# board.net
KiCad netlist of a schematic drawn in EAGLE
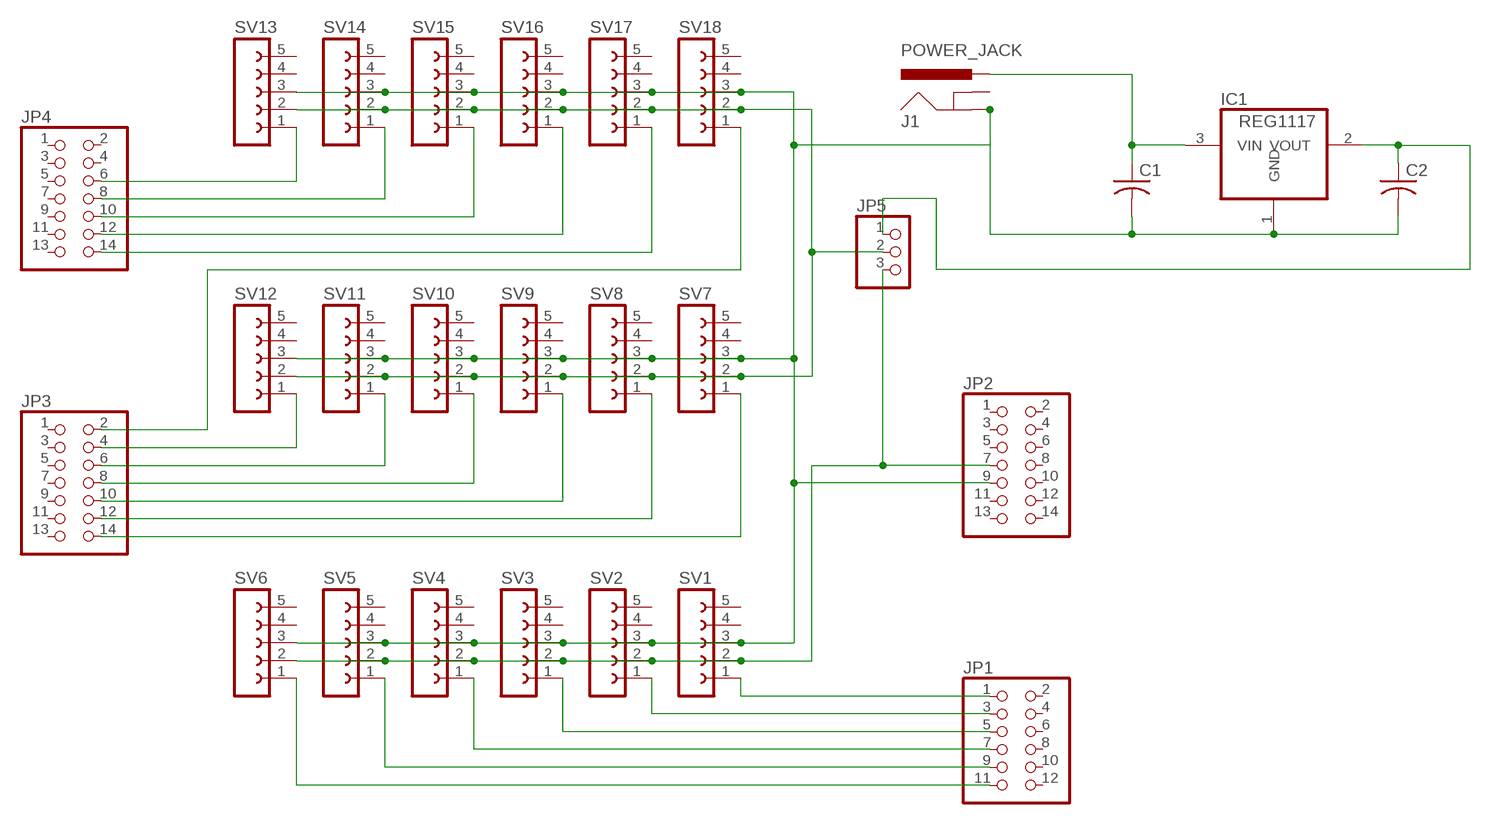
[diagram p0: schematic, sheet 1]

(export (version "E")
  (design (tool "Eeschema 10.0.6"))
  (components
    (comp (ref "C1")
      (value "C-US025-024X044")
      (footprint "eagle-import:C025-024X044")
      (libsource (lib "eagle-import") (part "C-US025-024X044"))
    )
    (comp (ref "C2")
      (value "C-US025-024X044")
      (footprint "eagle-import:C025-024X044")
      (libsource (lib "eagle-import") (part "C-US025-024X044"))
    )
    (comp (ref "IC1")
      (value "REG1117")
      (footprint "eagle-import:SOT223")
      (libsource (lib "eagle-import") (part "REG1117"))
    )
    (comp (ref "J1")
      (value "POWER_JACK")
      (footprint "eagle-import:POWER_JACK_PTH")
      (libsource (lib "eagle-import") (part "POWER_JACK"))
    )
    (comp (ref "JP1")
      (value "PINHD-2X6")
      (footprint "eagle-import:2X06")
      (libsource (lib "eagle-import") (part "PINHD-2X6"))
    )
    (comp (ref "JP2")
      (value "PINHD-2X7")
      (footprint "eagle-import:2X07")
      (libsource (lib "eagle-import") (part "PINHD-2X7"))
    )
    (comp (ref "JP3")
      (value "PINHD-2X7")
      (footprint "eagle-import:2X07")
      (libsource (lib "eagle-import") (part "PINHD-2X7"))
    )
    (comp (ref "JP4")
      (value "PINHD-2X7")
      (footprint "eagle-import:2X07")
      (libsource (lib "eagle-import") (part "PINHD-2X7"))
    )
    (comp (ref "JP5")
      (value "PINHD-1X3")
      (footprint "eagle-import:1X03")
      (libsource (lib "eagle-import") (part "PINHD-1X3"))
    )
    (comp (ref "SV1")
      (value "FE05-1")
      (footprint "eagle-import:FE05-1")
      (libsource (lib "eagle-import") (part "FE05-1"))
    )
    (comp (ref "SV2")
      (value "FE05-1")
      (footprint "eagle-import:FE05-1")
      (libsource (lib "eagle-import") (part "FE05-1"))
    )
    (comp (ref "SV3")
      (value "FE05-1")
      (footprint "eagle-import:FE05-1")
      (libsource (lib "eagle-import") (part "FE05-1"))
    )
    (comp (ref "SV4")
      (value "FE05-1")
      (footprint "eagle-import:FE05-1")
      (libsource (lib "eagle-import") (part "FE05-1"))
    )
    (comp (ref "SV5")
      (value "FE05-1")
      (footprint "eagle-import:FE05-1")
      (libsource (lib "eagle-import") (part "FE05-1"))
    )
    (comp (ref "SV6")
      (value "FE05-1")
      (footprint "eagle-import:FE05-1")
      (libsource (lib "eagle-import") (part "FE05-1"))
    )
    (comp (ref "SV7")
      (value "FE05-1")
      (footprint "eagle-import:FE05-1")
      (libsource (lib "eagle-import") (part "FE05-1"))
    )
    (comp (ref "SV8")
      (value "FE05-1")
      (footprint "eagle-import:FE05-1")
      (libsource (lib "eagle-import") (part "FE05-1"))
    )
    (comp (ref "SV9")
      (value "FE05-1")
      (footprint "eagle-import:FE05-1")
      (libsource (lib "eagle-import") (part "FE05-1"))
    )
    (comp (ref "SV10")
      (value "FE05-1")
      (footprint "eagle-import:FE05-1")
      (libsource (lib "eagle-import") (part "FE05-1"))
    )
    (comp (ref "SV11")
      (value "FE05-1")
      (footprint "eagle-import:FE05-1")
      (libsource (lib "eagle-import") (part "FE05-1"))
    )
    (comp (ref "SV12")
      (value "FE05-1")
      (footprint "eagle-import:FE05-1")
      (libsource (lib "eagle-import") (part "FE05-1"))
    )
    (comp (ref "SV13")
      (value "FE05-1")
      (footprint "eagle-import:FE05-1")
      (libsource (lib "eagle-import") (part "FE05-1"))
    )
    (comp (ref "SV14")
      (value "FE05-1")
      (footprint "eagle-import:FE05-1")
      (libsource (lib "eagle-import") (part "FE05-1"))
    )
    (comp (ref "SV15")
      (value "FE05-1")
      (footprint "eagle-import:FE05-1")
      (libsource (lib "eagle-import") (part "FE05-1"))
    )
    (comp (ref "SV16")
      (value "FE05-1")
      (footprint "eagle-import:FE05-1")
      (libsource (lib "eagle-import") (part "FE05-1"))
    )
    (comp (ref "SV17")
      (value "FE05-1")
      (footprint "eagle-import:FE05-1")
      (libsource (lib "eagle-import") (part "FE05-1"))
    )
    (comp (ref "SV18")
      (value "FE05-1")
      (footprint "eagle-import:FE05-1")
      (libsource (lib "eagle-import") (part "FE05-1"))
    )
  )
  (nets
    (net (code "1") (name "Net-(IC1-GND)") (class "Default")
      (node (ref "C1") (pin "2") (pinfunction "2_2") (pintype "passive"))
      (node (ref "C2") (pin "2") (pinfunction "2_2") (pintype "passive"))
      (node (ref "IC1") (pin "1") (pinfunction "GND_1") (pintype "power_in"))
      (node (ref "J1") (pin "GND") (pinfunction "GND_GND") (pintype "bidirectional"))
      (node (ref "JP2") (pin "9") (pinfunction "9_9") (pintype "passive"))
      (node (ref "SV1") (pin "3") (pinfunction "3_3") (pintype "passive"))
      (node (ref "SV10") (pin "3") (pinfunction "3_3") (pintype "passive"))
      (node (ref "SV11") (pin "3") (pinfunction "3_3") (pintype "passive"))
      (node (ref "SV12") (pin "3") (pinfunction "3_3") (pintype "passive"))
      (node (ref "SV13") (pin "3") (pinfunction "3_3") (pintype "passive"))
      (node (ref "SV14") (pin "3") (pinfunction "3_3") (pintype "passive"))
      (node (ref "SV15") (pin "3") (pinfunction "3_3") (pintype "passive"))
      (node (ref "SV16") (pin "3") (pinfunction "3_3") (pintype "passive"))
      (node (ref "SV17") (pin "3") (pinfunction "3_3") (pintype "passive"))
      (node (ref "SV18") (pin "3") (pinfunction "3_3") (pintype "passive"))
      (node (ref "SV2") (pin "3") (pinfunction "3_3") (pintype "passive"))
      (node (ref "SV3") (pin "3") (pinfunction "3_3") (pintype "passive"))
      (node (ref "SV4") (pin "3") (pinfunction "3_3") (pintype "passive"))
      (node (ref "SV5") (pin "3") (pinfunction "3_3") (pintype "passive"))
      (node (ref "SV6") (pin "3") (pinfunction "3_3") (pintype "passive"))
      (node (ref "SV7") (pin "3") (pinfunction "3_3") (pintype "passive"))
      (node (ref "SV8") (pin "3") (pinfunction "3_3") (pintype "passive"))
      (node (ref "SV9") (pin "3") (pinfunction "3_3") (pintype "passive"))
    )
    (net (code "2") (name "Net-(IC1-VIN)") (class "Default")
      (node (ref "C1") (pin "1") (pinfunction "1_1") (pintype "passive"))
      (node (ref "IC1") (pin "3") (pinfunction "VIN_3") (pintype "input"))
      (node (ref "J1") (pin "PWR") (pinfunction "PWR_PWR") (pintype "bidirectional"))
    )
    (net (code "3") (name "Net-(IC1-VOUT)") (class "Default")
      (node (ref "C2") (pin "1") (pinfunction "1_1") (pintype "passive"))
      (node (ref "IC1") (pin "2") (pinfunction "VOUT_2") (pintype "output"))
      (node (ref "JP5") (pin "1") (pinfunction "1_1") (pintype "passive"))
    )
    (net (code "4") (name "Net-(JP1-Pad1)") (class "Default")
      (node (ref "JP1") (pin "1") (pinfunction "1_1") (pintype "passive"))
      (node (ref "SV1") (pin "1") (pinfunction "1_1") (pintype "passive"))
    )
    (net (code "5") (name "Net-(JP1-Pad3)") (class "Default")
      (node (ref "JP1") (pin "3") (pinfunction "3_3") (pintype "passive"))
      (node (ref "SV2") (pin "1") (pinfunction "1_1") (pintype "passive"))
    )
    (net (code "6") (name "Net-(JP1-Pad5)") (class "Default")
      (node (ref "JP1") (pin "5") (pinfunction "5_5") (pintype "passive"))
      (node (ref "SV3") (pin "1") (pinfunction "1_1") (pintype "passive"))
    )
    (net (code "7") (name "Net-(JP1-Pad7)") (class "Default")
      (node (ref "JP1") (pin "7") (pinfunction "7_7") (pintype "passive"))
      (node (ref "SV4") (pin "1") (pinfunction "1_1") (pintype "passive"))
    )
    (net (code "8") (name "Net-(JP1-Pad9)") (class "Default")
      (node (ref "JP1") (pin "9") (pinfunction "9_9") (pintype "passive"))
      (node (ref "SV5") (pin "1") (pinfunction "1_1") (pintype "passive"))
    )
    (net (code "9") (name "Net-(JP1-Pad11)") (class "Default")
      (node (ref "JP1") (pin "11") (pinfunction "11_11") (pintype "passive"))
      (node (ref "SV6") (pin "1") (pinfunction "1_1") (pintype "passive"))
    )
    (net (code "10") (name "Net-(JP2-Pad7)") (class "Default")
      (node (ref "JP2") (pin "7") (pinfunction "7_7") (pintype "passive"))
      (node (ref "JP5") (pin "3") (pinfunction "3_3") (pintype "passive"))
      (node (ref "SV1") (pin "2") (pinfunction "2_2") (pintype "passive"))
      (node (ref "SV2") (pin "2") (pinfunction "2_2") (pintype "passive"))
      (node (ref "SV3") (pin "2") (pinfunction "2_2") (pintype "passive"))
      (node (ref "SV4") (pin "2") (pinfunction "2_2") (pintype "passive"))
      (node (ref "SV5") (pin "2") (pinfunction "2_2") (pintype "passive"))
      (node (ref "SV6") (pin "2") (pinfunction "2_2") (pintype "passive"))
    )
    (net (code "11") (name "Net-(JP3-Pad2)") (class "Default")
      (node (ref "JP3") (pin "2") (pinfunction "2_2") (pintype "passive"))
      (node (ref "SV18") (pin "1") (pinfunction "1_1") (pintype "passive"))
    )
    (net (code "12") (name "Net-(JP3-Pad4)") (class "Default")
      (node (ref "JP3") (pin "4") (pinfunction "4_4") (pintype "passive"))
      (node (ref "SV12") (pin "1") (pinfunction "1_1") (pintype "passive"))
    )
    (net (code "13") (name "Net-(JP3-Pad6)") (class "Default")
      (node (ref "JP3") (pin "6") (pinfunction "6_6") (pintype "passive"))
      (node (ref "SV11") (pin "1") (pinfunction "1_1") (pintype "passive"))
    )
    (net (code "14") (name "Net-(JP3-Pad8)") (class "Default")
      (node (ref "JP3") (pin "8") (pinfunction "8_8") (pintype "passive"))
      (node (ref "SV10") (pin "1") (pinfunction "1_1") (pintype "passive"))
    )
    (net (code "15") (name "Net-(JP3-Pad10)") (class "Default")
      (node (ref "JP3") (pin "10") (pinfunction "10_10") (pintype "passive"))
      (node (ref "SV9") (pin "1") (pinfunction "1_1") (pintype "passive"))
    )
    (net (code "16") (name "Net-(JP3-Pad12)") (class "Default")
      (node (ref "JP3") (pin "12") (pinfunction "12_12") (pintype "passive"))
      (node (ref "SV8") (pin "1") (pinfunction "1_1") (pintype "passive"))
    )
    (net (code "17") (name "Net-(JP3-Pad14)") (class "Default")
      (node (ref "JP3") (pin "14") (pinfunction "14_14") (pintype "passive"))
      (node (ref "SV7") (pin "1") (pinfunction "1_1") (pintype "passive"))
    )
    (net (code "18") (name "Net-(JP4-Pad6)") (class "Default")
      (node (ref "JP4") (pin "6") (pinfunction "6_6") (pintype "passive"))
      (node (ref "SV13") (pin "1") (pinfunction "1_1") (pintype "passive"))
    )
    (net (code "19") (name "Net-(JP4-Pad8)") (class "Default")
      (node (ref "JP4") (pin "8") (pinfunction "8_8") (pintype "passive"))
      (node (ref "SV14") (pin "1") (pinfunction "1_1") (pintype "passive"))
    )
    (net (code "20") (name "Net-(JP4-Pad10)") (class "Default")
      (node (ref "JP4") (pin "10") (pinfunction "10_10") (pintype "passive"))
      (node (ref "SV15") (pin "1") (pinfunction "1_1") (pintype "passive"))
    )
    (net (code "21") (name "Net-(JP4-Pad12)") (class "Default")
      (node (ref "JP4") (pin "12") (pinfunction "12_12") (pintype "passive"))
      (node (ref "SV16") (pin "1") (pinfunction "1_1") (pintype "passive"))
    )
    (net (code "22") (name "Net-(JP4-Pad14)") (class "Default")
      (node (ref "JP4") (pin "14") (pinfunction "14_14") (pintype "passive"))
      (node (ref "SV17") (pin "1") (pinfunction "1_1") (pintype "passive"))
    )
    (net (code "23") (name "Net-(JP5-Pad2)") (class "Default")
      (node (ref "JP5") (pin "2") (pinfunction "2_2") (pintype "passive"))
      (node (ref "SV10") (pin "2") (pinfunction "2_2") (pintype "passive"))
      (node (ref "SV11") (pin "2") (pinfunction "2_2") (pintype "passive"))
      (node (ref "SV12") (pin "2") (pinfunction "2_2") (pintype "passive"))
      (node (ref "SV13") (pin "2") (pinfunction "2_2") (pintype "passive"))
      (node (ref "SV14") (pin "2") (pinfunction "2_2") (pintype "passive"))
      (node (ref "SV15") (pin "2") (pinfunction "2_2") (pintype "passive"))
      (node (ref "SV16") (pin "2") (pinfunction "2_2") (pintype "passive"))
      (node (ref "SV17") (pin "2") (pinfunction "2_2") (pintype "passive"))
      (node (ref "SV18") (pin "2") (pinfunction "2_2") (pintype "passive"))
      (node (ref "SV7") (pin "2") (pinfunction "2_2") (pintype "passive"))
      (node (ref "SV8") (pin "2") (pinfunction "2_2") (pintype "passive"))
      (node (ref "SV9") (pin "2") (pinfunction "2_2") (pintype "passive"))
    )
    (net (code "24") (name "unconnected-(J1-PadGNDBREAK)") (class "Default")
      (node (ref "J1") (pin "GNDBREAK") (pinfunction "GNDBREAK_GNDBREAK") (pintype "bidirectional"))
    )
    (net (code "25") (name "unconnected-(JP1-Pad2)") (class "Default")
      (node (ref "JP1") (pin "2") (pinfunction "2_2") (pintype "passive"))
    )
    (net (code "26") (name "unconnected-(JP1-Pad4)") (class "Default")
      (node (ref "JP1") (pin "4") (pinfunction "4_4") (pintype "passive"))
    )
    (net (code "27") (name "unconnected-(JP1-Pad6)") (class "Default")
      (node (ref "JP1") (pin "6") (pinfunction "6_6") (pintype "passive"))
    )
    (net (code "28") (name "unconnected-(JP1-Pad8)") (class "Default")
      (node (ref "JP1") (pin "8") (pinfunction "8_8") (pintype "passive"))
    )
    (net (code "29") (name "unconnected-(JP1-Pad10)") (class "Default")
      (node (ref "JP1") (pin "10") (pinfunction "10_10") (pintype "passive"))
    )
    (net (code "30") (name "unconnected-(JP1-Pad12)") (class "Default")
      (node (ref "JP1") (pin "12") (pinfunction "12_12") (pintype "passive"))
    )
    (net (code "31") (name "unconnected-(JP2-Pad1)") (class "Default")
      (node (ref "JP2") (pin "1") (pinfunction "1_1") (pintype "passive"))
    )
    (net (code "32") (name "unconnected-(JP2-Pad2)") (class "Default")
      (node (ref "JP2") (pin "2") (pinfunction "2_2") (pintype "passive"))
    )
    (net (code "33") (name "unconnected-(JP2-Pad3)") (class "Default")
      (node (ref "JP2") (pin "3") (pinfunction "3_3") (pintype "passive"))
    )
    (net (code "34") (name "unconnected-(JP2-Pad4)") (class "Default")
      (node (ref "JP2") (pin "4") (pinfunction "4_4") (pintype "passive"))
    )
    (net (code "35") (name "unconnected-(JP2-Pad5)") (class "Default")
      (node (ref "JP2") (pin "5") (pinfunction "5_5") (pintype "passive"))
    )
    (net (code "36") (name "unconnected-(JP2-Pad6)") (class "Default")
      (node (ref "JP2") (pin "6") (pinfunction "6_6") (pintype "passive"))
    )
    (net (code "37") (name "unconnected-(JP2-Pad8)") (class "Default")
      (node (ref "JP2") (pin "8") (pinfunction "8_8") (pintype "passive"))
    )
    (net (code "38") (name "unconnected-(JP2-Pad10)") (class "Default")
      (node (ref "JP2") (pin "10") (pinfunction "10_10") (pintype "passive"))
    )
    (net (code "39") (name "unconnected-(JP2-Pad11)") (class "Default")
      (node (ref "JP2") (pin "11") (pinfunction "11_11") (pintype "passive"))
    )
    (net (code "40") (name "unconnected-(JP2-Pad12)") (class "Default")
      (node (ref "JP2") (pin "12") (pinfunction "12_12") (pintype "passive"))
    )
    (net (code "41") (name "unconnected-(JP2-Pad13)") (class "Default")
      (node (ref "JP2") (pin "13") (pinfunction "13_13") (pintype "passive"))
    )
    (net (code "42") (name "unconnected-(JP2-Pad14)") (class "Default")
      (node (ref "JP2") (pin "14") (pinfunction "14_14") (pintype "passive"))
    )
    (net (code "43") (name "unconnected-(JP3-Pad1)") (class "Default")
      (node (ref "JP3") (pin "1") (pinfunction "1_1") (pintype "passive"))
    )
    (net (code "44") (name "unconnected-(JP3-Pad3)") (class "Default")
      (node (ref "JP3") (pin "3") (pinfunction "3_3") (pintype "passive"))
    )
    (net (code "45") (name "unconnected-(JP3-Pad5)") (class "Default")
      (node (ref "JP3") (pin "5") (pinfunction "5_5") (pintype "passive"))
    )
    (net (code "46") (name "unconnected-(JP3-Pad7)") (class "Default")
      (node (ref "JP3") (pin "7") (pinfunction "7_7") (pintype "passive"))
    )
    (net (code "47") (name "unconnected-(JP3-Pad9)") (class "Default")
      (node (ref "JP3") (pin "9") (pinfunction "9_9") (pintype "passive"))
    )
    (net (code "48") (name "unconnected-(JP3-Pad11)") (class "Default")
      (node (ref "JP3") (pin "11") (pinfunction "11_11") (pintype "passive"))
    )
    (net (code "49") (name "unconnected-(JP3-Pad13)") (class "Default")
      (node (ref "JP3") (pin "13") (pinfunction "13_13") (pintype "passive"))
    )
    (net (code "50") (name "unconnected-(JP4-Pad1)") (class "Default")
      (node (ref "JP4") (pin "1") (pinfunction "1_1") (pintype "passive"))
    )
    (net (code "51") (name "unconnected-(JP4-Pad2)") (class "Default")
      (node (ref "JP4") (pin "2") (pinfunction "2_2") (pintype "passive"))
    )
    (net (code "52") (name "unconnected-(JP4-Pad3)") (class "Default")
      (node (ref "JP4") (pin "3") (pinfunction "3_3") (pintype "passive"))
    )
    (net (code "53") (name "unconnected-(JP4-Pad4)") (class "Default")
      (node (ref "JP4") (pin "4") (pinfunction "4_4") (pintype "passive"))
    )
    (net (code "54") (name "unconnected-(JP4-Pad5)") (class "Default")
      (node (ref "JP4") (pin "5") (pinfunction "5_5") (pintype "passive"))
    )
    (net (code "55") (name "unconnected-(JP4-Pad7)") (class "Default")
      (node (ref "JP4") (pin "7") (pinfunction "7_7") (pintype "passive"))
    )
    (net (code "56") (name "unconnected-(JP4-Pad9)") (class "Default")
      (node (ref "JP4") (pin "9") (pinfunction "9_9") (pintype "passive"))
    )
    (net (code "57") (name "unconnected-(JP4-Pad11)") (class "Default")
      (node (ref "JP4") (pin "11") (pinfunction "11_11") (pintype "passive"))
    )
    (net (code "58") (name "unconnected-(JP4-Pad13)") (class "Default")
      (node (ref "JP4") (pin "13") (pinfunction "13_13") (pintype "passive"))
    )
    (net (code "59") (name "unconnected-(SV1-Pad4)") (class "Default")
      (node (ref "SV1") (pin "4") (pinfunction "4_4") (pintype "passive"))
    )
    (net (code "60") (name "unconnected-(SV1-Pad5)") (class "Default")
      (node (ref "SV1") (pin "5") (pinfunction "5_5") (pintype "passive"))
    )
    (net (code "61") (name "unconnected-(SV2-Pad4)") (class "Default")
      (node (ref "SV2") (pin "4") (pinfunction "4_4") (pintype "passive"))
    )
    (net (code "62") (name "unconnected-(SV2-Pad5)") (class "Default")
      (node (ref "SV2") (pin "5") (pinfunction "5_5") (pintype "passive"))
    )
    (net (code "63") (name "unconnected-(SV3-Pad4)") (class "Default")
      (node (ref "SV3") (pin "4") (pinfunction "4_4") (pintype "passive"))
    )
    (net (code "64") (name "unconnected-(SV3-Pad5)") (class "Default")
      (node (ref "SV3") (pin "5") (pinfunction "5_5") (pintype "passive"))
    )
    (net (code "65") (name "unconnected-(SV4-Pad4)") (class "Default")
      (node (ref "SV4") (pin "4") (pinfunction "4_4") (pintype "passive"))
    )
    (net (code "66") (name "unconnected-(SV4-Pad5)") (class "Default")
      (node (ref "SV4") (pin "5") (pinfunction "5_5") (pintype "passive"))
    )
    (net (code "67") (name "unconnected-(SV5-Pad4)") (class "Default")
      (node (ref "SV5") (pin "4") (pinfunction "4_4") (pintype "passive"))
    )
    (net (code "68") (name "unconnected-(SV5-Pad5)") (class "Default")
      (node (ref "SV5") (pin "5") (pinfunction "5_5") (pintype "passive"))
    )
    (net (code "69") (name "unconnected-(SV6-Pad4)") (class "Default")
      (node (ref "SV6") (pin "4") (pinfunction "4_4") (pintype "passive"))
    )
    (net (code "70") (name "unconnected-(SV6-Pad5)") (class "Default")
      (node (ref "SV6") (pin "5") (pinfunction "5_5") (pintype "passive"))
    )
    (net (code "71") (name "unconnected-(SV7-Pad4)") (class "Default")
      (node (ref "SV7") (pin "4") (pinfunction "4_4") (pintype "passive"))
    )
    (net (code "72") (name "unconnected-(SV7-Pad5)") (class "Default")
      (node (ref "SV7") (pin "5") (pinfunction "5_5") (pintype "passive"))
    )
    (net (code "73") (name "unconnected-(SV8-Pad4)") (class "Default")
      (node (ref "SV8") (pin "4") (pinfunction "4_4") (pintype "passive"))
    )
    (net (code "74") (name "unconnected-(SV8-Pad5)") (class "Default")
      (node (ref "SV8") (pin "5") (pinfunction "5_5") (pintype "passive"))
    )
    (net (code "75") (name "unconnected-(SV9-Pad4)") (class "Default")
      (node (ref "SV9") (pin "4") (pinfunction "4_4") (pintype "passive"))
    )
    (net (code "76") (name "unconnected-(SV9-Pad5)") (class "Default")
      (node (ref "SV9") (pin "5") (pinfunction "5_5") (pintype "passive"))
    )
    (net (code "77") (name "unconnected-(SV10-Pad4)") (class "Default")
      (node (ref "SV10") (pin "4") (pinfunction "4_4") (pintype "passive"))
    )
    (net (code "78") (name "unconnected-(SV10-Pad5)") (class "Default")
      (node (ref "SV10") (pin "5") (pinfunction "5_5") (pintype "passive"))
    )
    (net (code "79") (name "unconnected-(SV11-Pad4)") (class "Default")
      (node (ref "SV11") (pin "4") (pinfunction "4_4") (pintype "passive"))
    )
    (net (code "80") (name "unconnected-(SV11-Pad5)") (class "Default")
      (node (ref "SV11") (pin "5") (pinfunction "5_5") (pintype "passive"))
    )
    (net (code "81") (name "unconnected-(SV12-Pad4)") (class "Default")
      (node (ref "SV12") (pin "4") (pinfunction "4_4") (pintype "passive"))
    )
    (net (code "82") (name "unconnected-(SV12-Pad5)") (class "Default")
      (node (ref "SV12") (pin "5") (pinfunction "5_5") (pintype "passive"))
    )
    (net (code "83") (name "unconnected-(SV13-Pad4)") (class "Default")
      (node (ref "SV13") (pin "4") (pinfunction "4_4") (pintype "passive"))
    )
    (net (code "84") (name "unconnected-(SV13-Pad5)") (class "Default")
      (node (ref "SV13") (pin "5") (pinfunction "5_5") (pintype "passive"))
    )
    (net (code "85") (name "unconnected-(SV14-Pad4)") (class "Default")
      (node (ref "SV14") (pin "4") (pinfunction "4_4") (pintype "passive"))
    )
    (net (code "86") (name "unconnected-(SV14-Pad5)") (class "Default")
      (node (ref "SV14") (pin "5") (pinfunction "5_5") (pintype "passive"))
    )
    (net (code "87") (name "unconnected-(SV15-Pad4)") (class "Default")
      (node (ref "SV15") (pin "4") (pinfunction "4_4") (pintype "passive"))
    )
    (net (code "88") (name "unconnected-(SV15-Pad5)") (class "Default")
      (node (ref "SV15") (pin "5") (pinfunction "5_5") (pintype "passive"))
    )
    (net (code "89") (name "unconnected-(SV16-Pad4)") (class "Default")
      (node (ref "SV16") (pin "4") (pinfunction "4_4") (pintype "passive"))
    )
    (net (code "90") (name "unconnected-(SV16-Pad5)") (class "Default")
      (node (ref "SV16") (pin "5") (pinfunction "5_5") (pintype "passive"))
    )
    (net (code "91") (name "unconnected-(SV17-Pad4)") (class "Default")
      (node (ref "SV17") (pin "4") (pinfunction "4_4") (pintype "passive"))
    )
    (net (code "92") (name "unconnected-(SV17-Pad5)") (class "Default")
      (node (ref "SV17") (pin "5") (pinfunction "5_5") (pintype "passive"))
    )
    (net (code "93") (name "unconnected-(SV18-Pad4)") (class "Default")
      (node (ref "SV18") (pin "4") (pinfunction "4_4") (pintype "passive"))
    )
    (net (code "94") (name "unconnected-(SV18-Pad5)") (class "Default")
      (node (ref "SV18") (pin "5") (pinfunction "5_5") (pintype "passive"))
    )
  )
)
